# PillEndo-MkI_MAIN5.net
KiCad netlist of a schematic drawn in EAGLE
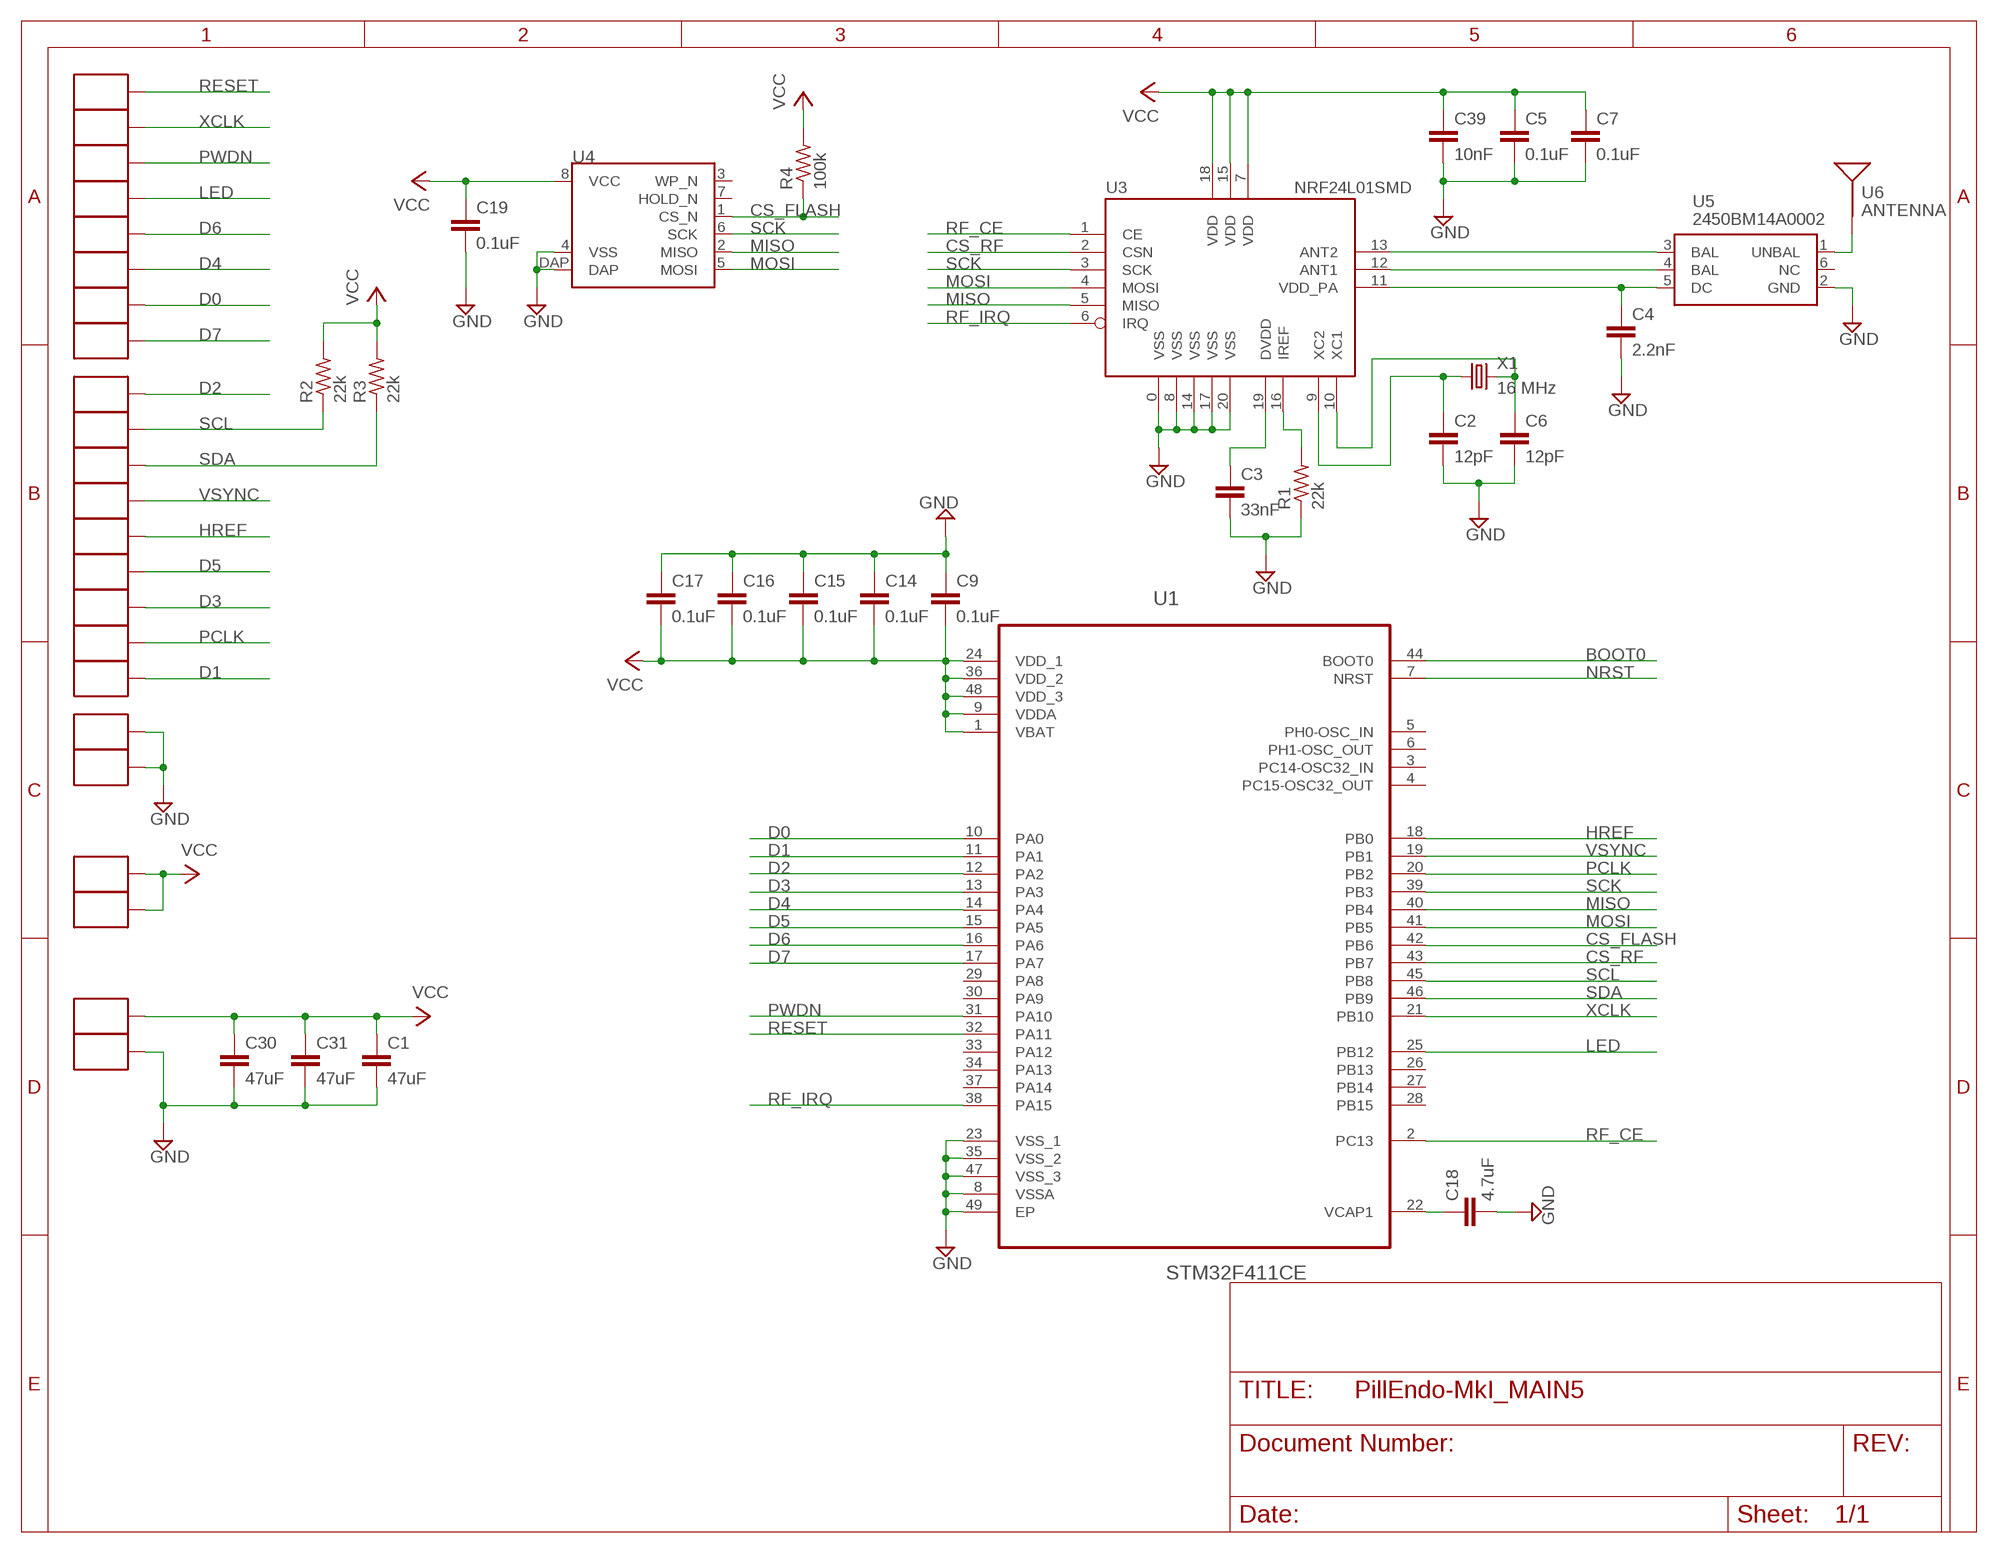
[diagram p0: schematic, sheet 1]

(export (version "E")
  (design (tool "Eeschema 10.0.6"))
  (components
    (comp (ref "C1")
      (value "47uF")
      (footprint "eagle-import:C0603")
      (libsource (lib "eagle-import") (part "C0603"))
    )
    (comp (ref "C2")
      (value "12pF")
      (footprint "eagle-import:C0402")
      (libsource (lib "eagle-import") (part "C0402"))
    )
    (comp (ref "C3")
      (value "33nF")
      (footprint "eagle-import:C0402")
      (libsource (lib "eagle-import") (part "C0402"))
    )
    (comp (ref "C4")
      (value "2.2nF")
      (footprint "eagle-import:C0402")
      (libsource (lib "eagle-import") (part "C0402"))
    )
    (comp (ref "C5")
      (value "0.1uF")
      (footprint "eagle-import:C0402")
      (libsource (lib "eagle-import") (part "C0402"))
    )
    (comp (ref "C6")
      (value "12pF")
      (footprint "eagle-import:C0402")
      (libsource (lib "eagle-import") (part "C0402"))
    )
    (comp (ref "C7")
      (value "0.1uF")
      (footprint "eagle-import:C0402")
      (libsource (lib "eagle-import") (part "C0402"))
    )
    (comp (ref "C9")
      (value "0.1uF")
      (footprint "eagle-import:C0402")
      (libsource (lib "eagle-import") (part "C0402"))
    )
    (comp (ref "C14")
      (value "0.1uF")
      (footprint "eagle-import:C0402")
      (libsource (lib "eagle-import") (part "C0402"))
    )
    (comp (ref "C15")
      (value "0.1uF")
      (footprint "eagle-import:C0402")
      (libsource (lib "eagle-import") (part "C0402"))
    )
    (comp (ref "C16")
      (value "0.1uF")
      (footprint "eagle-import:C0402")
      (libsource (lib "eagle-import") (part "C0402"))
    )
    (comp (ref "C17")
      (value "0.1uF")
      (footprint "eagle-import:C0402")
      (libsource (lib "eagle-import") (part "C0402"))
    )
    (comp (ref "C18")
      (value "4.7uF")
      (footprint "eagle-import:C0402")
      (libsource (lib "eagle-import") (part "C0402"))
    )
    (comp (ref "C19")
      (value "0.1uF")
      (footprint "eagle-import:C0402")
      (libsource (lib "eagle-import") (part "C0402"))
    )
    (comp (ref "C30")
      (value "47uF")
      (footprint "eagle-import:C0603")
      (libsource (lib "eagle-import") (part "C0603"))
    )
    (comp (ref "C31")
      (value "47uF")
      (footprint "eagle-import:C0603")
      (libsource (lib "eagle-import") (part "C0603"))
    )
    (comp (ref "C39")
      (value "10nF")
      (footprint "eagle-import:C0402")
      (libsource (lib "eagle-import") (part "C0402"))
    )
    (comp (ref "R1")
      (value "22k")
      (footprint "eagle-import:R0402")
      (libsource (lib "eagle-import") (part "R0402"))
    )
    (comp (ref "R2")
      (value "22k")
      (footprint "eagle-import:R0402")
      (libsource (lib "eagle-import") (part "R0402"))
    )
    (comp (ref "R3")
      (value "22k")
      (footprint "eagle-import:R0402")
      (libsource (lib "eagle-import") (part "R0402"))
    )
    (comp (ref "R4")
      (value "100k")
      (footprint "eagle-import:R0402")
      (libsource (lib "eagle-import") (part "R0402"))
    )
    (comp (ref "TP1")
      (value "TP_0.8X1.2")
      (footprint "eagle-import:TP_0.8X1.2")
      (libsource (lib "eagle-import") (part "TP_0.8X1.2"))
    )
    (comp (ref "TP2")
      (value "TP_0.8X1.2")
      (footprint "eagle-import:TP_0.8X1.2")
      (libsource (lib "eagle-import") (part "TP_0.8X1.2"))
    )
    (comp (ref "TP3")
      (value "TP_0.8X1.2")
      (footprint "eagle-import:TP_0.8X1.2")
      (libsource (lib "eagle-import") (part "TP_0.8X1.2"))
    )
    (comp (ref "TP4")
      (value "TP_0.8X1.2")
      (footprint "eagle-import:TP_0.8X1.2")
      (libsource (lib "eagle-import") (part "TP_0.8X1.2"))
    )
    (comp (ref "TP5")
      (value "TP_0.8X1.2")
      (footprint "eagle-import:TP_0.8X1.2")
      (libsource (lib "eagle-import") (part "TP_0.8X1.2"))
    )
    (comp (ref "TP6")
      (value "TP_0.8X1.2")
      (footprint "eagle-import:TP_0.8X1.2")
      (libsource (lib "eagle-import") (part "TP_0.8X1.2"))
    )
    (comp (ref "TP7")
      (value "TP_0.8X1.2")
      (footprint "eagle-import:TP_0.8X1.2")
      (libsource (lib "eagle-import") (part "TP_0.8X1.2"))
    )
    (comp (ref "TP8")
      (value "TP_0.8X1.2")
      (footprint "eagle-import:TP_0.8X1.2")
      (libsource (lib "eagle-import") (part "TP_0.8X1.2"))
    )
    (comp (ref "TP9")
      (value "TP_0.8X1.2")
      (footprint "eagle-import:TP_0.8X1.2")
      (libsource (lib "eagle-import") (part "TP_0.8X1.2"))
    )
    (comp (ref "TP10")
      (value "TP_TP1.0X2.2")
      (footprint "eagle-import:TP_1.0X2.2")
      (libsource (lib "eagle-import") (part "TP_TP1.0X2.2"))
    )
    (comp (ref "TP11")
      (value "TP_0.8X1.2")
      (footprint "eagle-import:TP_0.8X1.2")
      (libsource (lib "eagle-import") (part "TP_0.8X1.2"))
    )
    (comp (ref "TP12")
      (value "TP_TP1.0X2.2")
      (footprint "eagle-import:TP_1.0X2.2")
      (libsource (lib "eagle-import") (part "TP_TP1.0X2.2"))
    )
    (comp (ref "TP13")
      (value "TP_0.8X1.2")
      (footprint "eagle-import:TP_0.8X1.2")
      (libsource (lib "eagle-import") (part "TP_0.8X1.2"))
    )
    (comp (ref "TP14")
      (value "TP_0.8X1.2")
      (footprint "eagle-import:TP_0.8X1.2")
      (libsource (lib "eagle-import") (part "TP_0.8X1.2"))
    )
    (comp (ref "TP15")
      (value "TP_0.8X1.2")
      (footprint "eagle-import:TP_0.8X1.2")
      (libsource (lib "eagle-import") (part "TP_0.8X1.2"))
    )
    (comp (ref "TP16")
      (value "TP_0.8X1.2")
      (footprint "eagle-import:TP_0.8X1.2")
      (libsource (lib "eagle-import") (part "TP_0.8X1.2"))
    )
    (comp (ref "TP17")
      (value "TP_TP1.0X2.2")
      (footprint "eagle-import:TP_1.0X2.2")
      (libsource (lib "eagle-import") (part "TP_TP1.0X2.2"))
    )
    (comp (ref "TP18")
      (value "TP_TP1.0X2.2")
      (footprint "eagle-import:TP_1.0X2.2")
      (libsource (lib "eagle-import") (part "TP_TP1.0X2.2"))
    )
    (comp (ref "TP19")
      (value "TP_TP1.0X2.2")
      (footprint "eagle-import:TP_1.0X2.2")
      (libsource (lib "eagle-import") (part "TP_TP1.0X2.2"))
    )
    (comp (ref "TP20")
      (value "TP_TP1.0X2.2")
      (footprint "eagle-import:TP_1.0X2.2")
      (libsource (lib "eagle-import") (part "TP_TP1.0X2.2"))
    )
    (comp (ref "TP33")
      (value "TP_0.8X1.2")
      (footprint "eagle-import:TP_0.8X1.2")
      (libsource (lib "eagle-import") (part "TP_0.8X1.2"))
    )
    (comp (ref "TP34")
      (value "TP_0.8X1.2")
      (footprint "eagle-import:TP_0.8X1.2")
      (libsource (lib "eagle-import") (part "TP_0.8X1.2"))
    )
    (comp (ref "TP35")
      (value "TP_0.8X1.2")
      (footprint "eagle-import:TP_0.8X1.2")
      (libsource (lib "eagle-import") (part "TP_0.8X1.2"))
    )
    (comp (ref "U1")
      (value "STM32F411CE")
      (footprint "eagle-import:QFN50P700X700X60-49N")
      (libsource (lib "eagle-import") (part "STM32F411CE"))
    )
    (comp (ref "U3")
      (value "NRF24L01SMD")
      (footprint "eagle-import:QFN20")
      (libsource (lib "eagle-import") (part "NRF24L01SMD"))
    )
    (comp (ref "U4")
      (value "S25FL256S")
      (footprint "eagle-import:WSON_6X8")
      (libsource (lib "eagle-import") (part "S25FL256S"))
    )
    (comp (ref "U5")
      (value "2450BM14A0002")
      (footprint "eagle-import:2450BM14A0002T")
      (libsource (lib "eagle-import") (part "2450BM14A0002"))
    )
    (comp (ref "U6")
      (value "ANTENNA")
      (footprint "eagle-import:2450AT18A100")
      (libsource (lib "eagle-import") (part "ANTENNA"))
    )
    (comp (ref "X1")
      (value "16 MHz")
      (footprint "eagle-import:CRYSTAL_FA20H")
      (libsource (lib "eagle-import") (part "CRYSTAL_FA-20H"))
    )
  )
  (nets
    (net (code "1") (name "/BOOT0") (class "Default")
      (node (ref "U1") (pin "44") (pinfunction "BOOT0_44") (pintype "input"))
    )
    (net (code "2") (name "/CS_FLASH") (class "Default")
      (node (ref "R4") (pin "1") (pinfunction "1_1") (pintype "passive"))
      (node (ref "U1") (pin "42") (pinfunction "PB6_42") (pintype "bidirectional"))
      (node (ref "U4") (pin "1") (pinfunction "CS_N_1") (pintype "bidirectional"))
    )
    (net (code "3") (name "/CS_RF") (class "Default")
      (node (ref "U1") (pin "43") (pinfunction "PB7_43") (pintype "bidirectional"))
      (node (ref "U3") (pin "2") (pinfunction "CSN_2") (pintype "input"))
    )
    (net (code "4") (name "/D0") (class "Default")
      (node (ref "TP7") (pin "P$1") (pinfunction "P$1_P$1") (pintype "passive"))
      (node (ref "U1") (pin "10") (pinfunction "PA0_10") (pintype "bidirectional"))
    )
    (net (code "5") (name "/D1") (class "Default")
      (node (ref "TP34") (pin "P$1") (pinfunction "P$1_P$1") (pintype "passive"))
      (node (ref "U1") (pin "11") (pinfunction "PA1_11") (pintype "bidirectional"))
    )
    (net (code "6") (name "/D2") (class "Default")
      (node (ref "TP9") (pin "P$1") (pinfunction "P$1_P$1") (pintype "passive"))
      (node (ref "U1") (pin "12") (pinfunction "PA2_12") (pintype "bidirectional"))
    )
    (net (code "7") (name "/D3") (class "Default")
      (node (ref "TP16") (pin "P$1") (pinfunction "P$1_P$1") (pintype "passive"))
      (node (ref "U1") (pin "13") (pinfunction "PA3_13") (pintype "bidirectional"))
    )
    (net (code "8") (name "/D4") (class "Default")
      (node (ref "TP6") (pin "P$1") (pinfunction "P$1_P$1") (pintype "passive"))
      (node (ref "U1") (pin "14") (pinfunction "PA4_14") (pintype "bidirectional"))
    )
    (net (code "9") (name "/D5") (class "Default")
      (node (ref "TP15") (pin "P$1") (pinfunction "P$1_P$1") (pintype "passive"))
      (node (ref "U1") (pin "15") (pinfunction "PA5_15") (pintype "bidirectional"))
    )
    (net (code "10") (name "/D6") (class "Default")
      (node (ref "TP5") (pin "P$1") (pinfunction "P$1_P$1") (pintype "passive"))
      (node (ref "U1") (pin "16") (pinfunction "PA6_16") (pintype "bidirectional"))
    )
    (net (code "11") (name "/D7") (class "Default")
      (node (ref "TP8") (pin "P$1") (pinfunction "P$1_P$1") (pintype "passive"))
      (node (ref "U1") (pin "17") (pinfunction "PA7_17") (pintype "bidirectional"))
    )
    (net (code "12") (name "/HREF") (class "Default")
      (node (ref "TP14") (pin "P$1") (pinfunction "P$1_P$1") (pintype "passive"))
      (node (ref "U1") (pin "18") (pinfunction "PB0_18") (pintype "bidirectional"))
    )
    (net (code "13") (name "/LED") (class "Default")
      (node (ref "TP4") (pin "P$1") (pinfunction "P$1_P$1") (pintype "passive"))
      (node (ref "U1") (pin "25") (pinfunction "PB12_25") (pintype "bidirectional"))
    )
    (net (code "14") (name "/MISO") (class "Default")
      (node (ref "U1") (pin "40") (pinfunction "PB4_40") (pintype "bidirectional"))
      (node (ref "U3") (pin "5") (pinfunction "MISO_5") (pintype "output"))
      (node (ref "U4") (pin "2") (pinfunction "MISO_2") (pintype "bidirectional"))
    )
    (net (code "15") (name "/MOSI") (class "Default")
      (node (ref "U1") (pin "41") (pinfunction "PB5_41") (pintype "bidirectional"))
      (node (ref "U3") (pin "4") (pinfunction "MOSI_4") (pintype "input"))
      (node (ref "U4") (pin "5") (pinfunction "MOSI_5") (pintype "bidirectional"))
    )
    (net (code "16") (name "/NRST") (class "Default")
      (node (ref "U1") (pin "7") (pinfunction "NRST_7") (pintype "bidirectional"))
    )
    (net (code "17") (name "/PCLK") (class "Default")
      (node (ref "TP33") (pin "P$1") (pinfunction "P$1_P$1") (pintype "passive"))
      (node (ref "U1") (pin "20") (pinfunction "PB2_20") (pintype "bidirectional"))
    )
    (net (code "18") (name "/PWDN") (class "Default")
      (node (ref "TP3") (pin "P$1") (pinfunction "P$1_P$1") (pintype "passive"))
      (node (ref "U1") (pin "31") (pinfunction "PA10_31") (pintype "bidirectional"))
    )
    (net (code "19") (name "/RESET") (class "Default")
      (node (ref "TP1") (pin "P$1") (pinfunction "P$1_P$1") (pintype "passive"))
      (node (ref "U1") (pin "32") (pinfunction "PA11_32") (pintype "bidirectional"))
    )
    (net (code "20") (name "/RF_CE") (class "Default")
      (node (ref "U1") (pin "2") (pinfunction "PC13_2") (pintype "bidirectional"))
      (node (ref "U3") (pin "1") (pinfunction "CE_1") (pintype "input"))
    )
    (net (code "21") (name "/RF_IRQ") (class "Default")
      (node (ref "U1") (pin "38") (pinfunction "PA15_38") (pintype "bidirectional"))
      (node (ref "U3") (pin "6") (pinfunction "IRQ_6") (pintype "output"))
    )
    (net (code "22") (name "/SCK") (class "Default")
      (node (ref "U1") (pin "39") (pinfunction "PB3_39") (pintype "bidirectional"))
      (node (ref "U3") (pin "3") (pinfunction "SCK_3") (pintype "input"))
      (node (ref "U4") (pin "6") (pinfunction "SCK_6") (pintype "bidirectional"))
    )
    (net (code "23") (name "/SCL") (class "Default")
      (node (ref "R2") (pin "1") (pinfunction "1_1") (pintype "passive"))
      (node (ref "TP11") (pin "P$1") (pinfunction "P$1_P$1") (pintype "passive"))
      (node (ref "U1") (pin "45") (pinfunction "PB8_45") (pintype "bidirectional"))
    )
    (net (code "24") (name "/SDA") (class "Default")
      (node (ref "R3") (pin "1") (pinfunction "1_1") (pintype "passive"))
      (node (ref "TP35") (pin "P$1") (pinfunction "P$1_P$1") (pintype "passive"))
      (node (ref "U1") (pin "46") (pinfunction "PB9_46") (pintype "bidirectional"))
    )
    (net (code "25") (name "/VSYNC") (class "Default")
      (node (ref "TP13") (pin "P$1") (pinfunction "P$1_P$1") (pintype "passive"))
      (node (ref "U1") (pin "19") (pinfunction "PB1_19") (pintype "bidirectional"))
    )
    (net (code "26") (name "/XCLK") (class "Default")
      (node (ref "TP2") (pin "P$1") (pinfunction "P$1_P$1") (pintype "passive"))
      (node (ref "U1") (pin "21") (pinfunction "PB10_21") (pintype "bidirectional"))
    )
    (net (code "27") (name "GND") (class "Default")
      (node (ref "C1") (pin "2") (pinfunction "2_2") (pintype "passive"))
      (node (ref "C14") (pin "1") (pinfunction "1_1") (pintype "passive"))
      (node (ref "C15") (pin "1") (pinfunction "1_1") (pintype "passive"))
      (node (ref "C16") (pin "1") (pinfunction "1_1") (pintype "passive"))
      (node (ref "C17") (pin "1") (pinfunction "1_1") (pintype "passive"))
      (node (ref "C18") (pin "2") (pinfunction "2_2") (pintype "passive"))
      (node (ref "C19") (pin "2") (pinfunction "2_2") (pintype "passive"))
      (node (ref "C2") (pin "2") (pinfunction "2_2") (pintype "passive"))
      (node (ref "C3") (pin "2") (pinfunction "2_2") (pintype "passive"))
      (node (ref "C30") (pin "2") (pinfunction "2_2") (pintype "passive"))
      (node (ref "C31") (pin "2") (pinfunction "2_2") (pintype "passive"))
      (node (ref "C39") (pin "2") (pinfunction "2_2") (pintype "passive"))
      (node (ref "C4") (pin "2") (pinfunction "2_2") (pintype "passive"))
      (node (ref "C5") (pin "2") (pinfunction "2_2") (pintype "passive"))
      (node (ref "C6") (pin "2") (pinfunction "2_2") (pintype "passive"))
      (node (ref "C7") (pin "2") (pinfunction "2_2") (pintype "passive"))
      (node (ref "C9") (pin "1") (pinfunction "1_1") (pintype "passive"))
      (node (ref "R1") (pin "1") (pinfunction "1_1") (pintype "passive"))
      (node (ref "TP10") (pin "P$1") (pinfunction "P$1_P$1") (pintype "passive"))
      (node (ref "TP12") (pin "P$1") (pinfunction "P$1_P$1") (pintype "passive"))
      (node (ref "TP17") (pin "P$1") (pinfunction "P$1_P$1") (pintype "passive"))
      (node (ref "U1") (pin "23") (pinfunction "VSS_1_23") (pintype "power_in"))
      (node (ref "U1") (pin "35") (pinfunction "VSS_2_35") (pintype "power_in"))
      (node (ref "U1") (pin "47") (pinfunction "VSS_3_47") (pintype "power_in"))
      (node (ref "U1") (pin "49") (pinfunction "EP_49") (pintype "passive"))
      (node (ref "U1") (pin "8") (pinfunction "VSSA_8") (pintype "power_in"))
      (node (ref "U3") (pin "0") (pinfunction "VSS_0") (pintype "power_in"))
      (node (ref "U3") (pin "14") (pinfunction "VSS_14") (pintype "power_in"))
      (node (ref "U3") (pin "17") (pinfunction "VSS_17") (pintype "power_in"))
      (node (ref "U3") (pin "20") (pinfunction "VSS_20") (pintype "power_in"))
      (node (ref "U3") (pin "8") (pinfunction "VSS_8") (pintype "power_in"))
      (node (ref "U4") (pin "4") (pinfunction "VSS_4") (pintype "bidirectional"))
      (node (ref "U4") (pin "DAP") (pinfunction "DAP_DAP") (pintype "bidirectional"))
      (node (ref "U5") (pin "2") (pinfunction "GND_2") (pintype "passive"))
    )
    (net (code "28") (name "Net-(U1-VCAP1)") (class "Default")
      (node (ref "C18") (pin "1") (pinfunction "1_1") (pintype "passive"))
      (node (ref "U1") (pin "22") (pinfunction "VCAP1_22") (pintype "bidirectional"))
    )
    (net (code "29") (name "Net-(U3-ANT1)") (class "Default")
      (node (ref "U3") (pin "12") (pinfunction "ANT1_12") (pintype "output"))
      (node (ref "U5") (pin "4") (pinfunction "BAL_4") (pintype "passive"))
    )
    (net (code "30") (name "Net-(U3-ANT2)") (class "Default")
      (node (ref "U3") (pin "13") (pinfunction "ANT2_13") (pintype "output"))
      (node (ref "U5") (pin "3") (pinfunction "BAL_3") (pintype "passive"))
    )
    (net (code "31") (name "Net-(U3-DVDD)") (class "Default")
      (node (ref "C3") (pin "1") (pinfunction "1_1") (pintype "passive"))
      (node (ref "U3") (pin "19") (pinfunction "DVDD_19") (pintype "power_in"))
    )
    (net (code "32") (name "Net-(U3-IREF)") (class "Default")
      (node (ref "R1") (pin "2") (pinfunction "2_2") (pintype "passive"))
      (node (ref "U3") (pin "16") (pinfunction "IREF_16") (pintype "input"))
    )
    (net (code "33") (name "Net-(U3-VDD_PA)") (class "Default")
      (node (ref "C4") (pin "1") (pinfunction "1_1") (pintype "passive"))
      (node (ref "U3") (pin "11") (pinfunction "VDD_PA_11") (pintype "power_in"))
      (node (ref "U5") (pin "5") (pinfunction "DC_5") (pintype "passive"))
    )
    (net (code "34") (name "Net-(U3-XC1)") (class "Default")
      (node (ref "C6") (pin "1") (pinfunction "1_1") (pintype "passive"))
      (node (ref "U3") (pin "10") (pinfunction "XC1_10") (pintype "input"))
      (node (ref "X1") (pin "3") (pinfunction "2_3") (pintype "passive"))
    )
    (net (code "35") (name "Net-(U3-XC2)") (class "Default")
      (node (ref "C2") (pin "1") (pinfunction "1_1") (pintype "passive"))
      (node (ref "U3") (pin "9") (pinfunction "XC2_9") (pintype "input"))
      (node (ref "X1") (pin "1") (pinfunction "1_1") (pintype "passive"))
    )
    (net (code "36") (name "Net-(U5-UNBAL)") (class "Default")
      (node (ref "U5") (pin "1") (pinfunction "UNBAL_1") (pintype "passive"))
      (node (ref "U6") (pin "1") (pinfunction "SIGNAL_1") (pintype "bidirectional"))
    )
    (net (code "37") (name "VCC") (class "Default")
      (node (ref "C1") (pin "1") (pinfunction "1_1") (pintype "passive"))
      (node (ref "C14") (pin "2") (pinfunction "2_2") (pintype "passive"))
      (node (ref "C15") (pin "2") (pinfunction "2_2") (pintype "passive"))
      (node (ref "C16") (pin "2") (pinfunction "2_2") (pintype "passive"))
      (node (ref "C17") (pin "2") (pinfunction "2_2") (pintype "passive"))
      (node (ref "C19") (pin "1") (pinfunction "1_1") (pintype "passive"))
      (node (ref "C30") (pin "1") (pinfunction "1_1") (pintype "passive"))
      (node (ref "C31") (pin "1") (pinfunction "1_1") (pintype "passive"))
      (node (ref "C39") (pin "1") (pinfunction "1_1") (pintype "passive"))
      (node (ref "C5") (pin "1") (pinfunction "1_1") (pintype "passive"))
      (node (ref "C7") (pin "1") (pinfunction "1_1") (pintype "passive"))
      (node (ref "C9") (pin "2") (pinfunction "2_2") (pintype "passive"))
      (node (ref "R2") (pin "2") (pinfunction "2_2") (pintype "passive"))
      (node (ref "R3") (pin "2") (pinfunction "2_2") (pintype "passive"))
      (node (ref "R4") (pin "2") (pinfunction "2_2") (pintype "passive"))
      (node (ref "TP18") (pin "P$1") (pinfunction "P$1_P$1") (pintype "passive"))
      (node (ref "TP19") (pin "P$1") (pinfunction "P$1_P$1") (pintype "passive"))
      (node (ref "TP20") (pin "P$1") (pinfunction "P$1_P$1") (pintype "passive"))
      (node (ref "U1") (pin "1") (pinfunction "VBAT_1") (pintype "power_in"))
      (node (ref "U1") (pin "24") (pinfunction "VDD_1_24") (pintype "power_in"))
      (node (ref "U1") (pin "36") (pinfunction "VDD_2_36") (pintype "power_in"))
      (node (ref "U1") (pin "48") (pinfunction "VDD_3_48") (pintype "power_in"))
      (node (ref "U1") (pin "9") (pinfunction "VDDA_9") (pintype "power_in"))
      (node (ref "U3") (pin "15") (pinfunction "VDD_15") (pintype "power_in"))
      (node (ref "U3") (pin "18") (pinfunction "VDD_18") (pintype "power_in"))
      (node (ref "U3") (pin "7") (pinfunction "VDD_7") (pintype "power_in"))
      (node (ref "U4") (pin "8") (pinfunction "VCC_8") (pintype "bidirectional"))
    )
    (net (code "38") (name "unconnected-(U1-PA8-Pad29)") (class "Default")
      (node (ref "U1") (pin "29") (pinfunction "PA8_29") (pintype "bidirectional"))
    )
    (net (code "39") (name "unconnected-(U1-PA9-Pad30)") (class "Default")
      (node (ref "U1") (pin "30") (pinfunction "PA9_30") (pintype "bidirectional"))
    )
    (net (code "40") (name "unconnected-(U1-PA12-Pad33)") (class "Default")
      (node (ref "U1") (pin "33") (pinfunction "PA12_33") (pintype "bidirectional"))
    )
    (net (code "41") (name "unconnected-(U1-PA13-Pad34)") (class "Default")
      (node (ref "U1") (pin "34") (pinfunction "PA13_34") (pintype "bidirectional"))
    )
    (net (code "42") (name "unconnected-(U1-PA14-Pad37)") (class "Default")
      (node (ref "U1") (pin "37") (pinfunction "PA14_37") (pintype "bidirectional"))
    )
    (net (code "43") (name "unconnected-(U1-PB13-Pad26)") (class "Default")
      (node (ref "U1") (pin "26") (pinfunction "PB13_26") (pintype "bidirectional"))
    )
    (net (code "44") (name "unconnected-(U1-PB14-Pad27)") (class "Default")
      (node (ref "U1") (pin "27") (pinfunction "PB14_27") (pintype "bidirectional"))
    )
    (net (code "45") (name "unconnected-(U1-PB15-Pad28)") (class "Default")
      (node (ref "U1") (pin "28") (pinfunction "PB15_28") (pintype "bidirectional"))
    )
    (net (code "46") (name "unconnected-(U1-PC14-OSC32_IN-Pad3)") (class "Default")
      (node (ref "U1") (pin "3") (pinfunction "PC14-OSC32_IN_3") (pintype "bidirectional"))
    )
    (net (code "47") (name "unconnected-(U1-PC15-OSC32_OUT-Pad4)") (class "Default")
      (node (ref "U1") (pin "4") (pinfunction "PC15-OSC32_OUT_4") (pintype "bidirectional"))
    )
    (net (code "48") (name "unconnected-(U1-PH0-OSC_IN-Pad5)") (class "Default")
      (node (ref "U1") (pin "5") (pinfunction "PH0-OSC_IN_5") (pintype "input"))
    )
    (net (code "49") (name "unconnected-(U1-PH1-OSC_OUT-Pad6)") (class "Default")
      (node (ref "U1") (pin "6") (pinfunction "PH1-OSC_OUT_6") (pintype "output"))
    )
    (net (code "50") (name "unconnected-(U4-HOLD_N-Pad7)") (class "Default")
      (node (ref "U4") (pin "7") (pinfunction "HOLD_N_7") (pintype "bidirectional"))
    )
    (net (code "51") (name "unconnected-(U4-WP_N-Pad3)") (class "Default")
      (node (ref "U4") (pin "3") (pinfunction "WP_N_3") (pintype "bidirectional"))
    )
    (net (code "52") (name "unconnected-(U5-NC-Pad6)") (class "Default")
      (node (ref "U5") (pin "6") (pinfunction "NC_6") (pintype "passive"))
    )
  )
)
